# connectors.net
KiCad netlist of a schematic drawn in Altium Designer
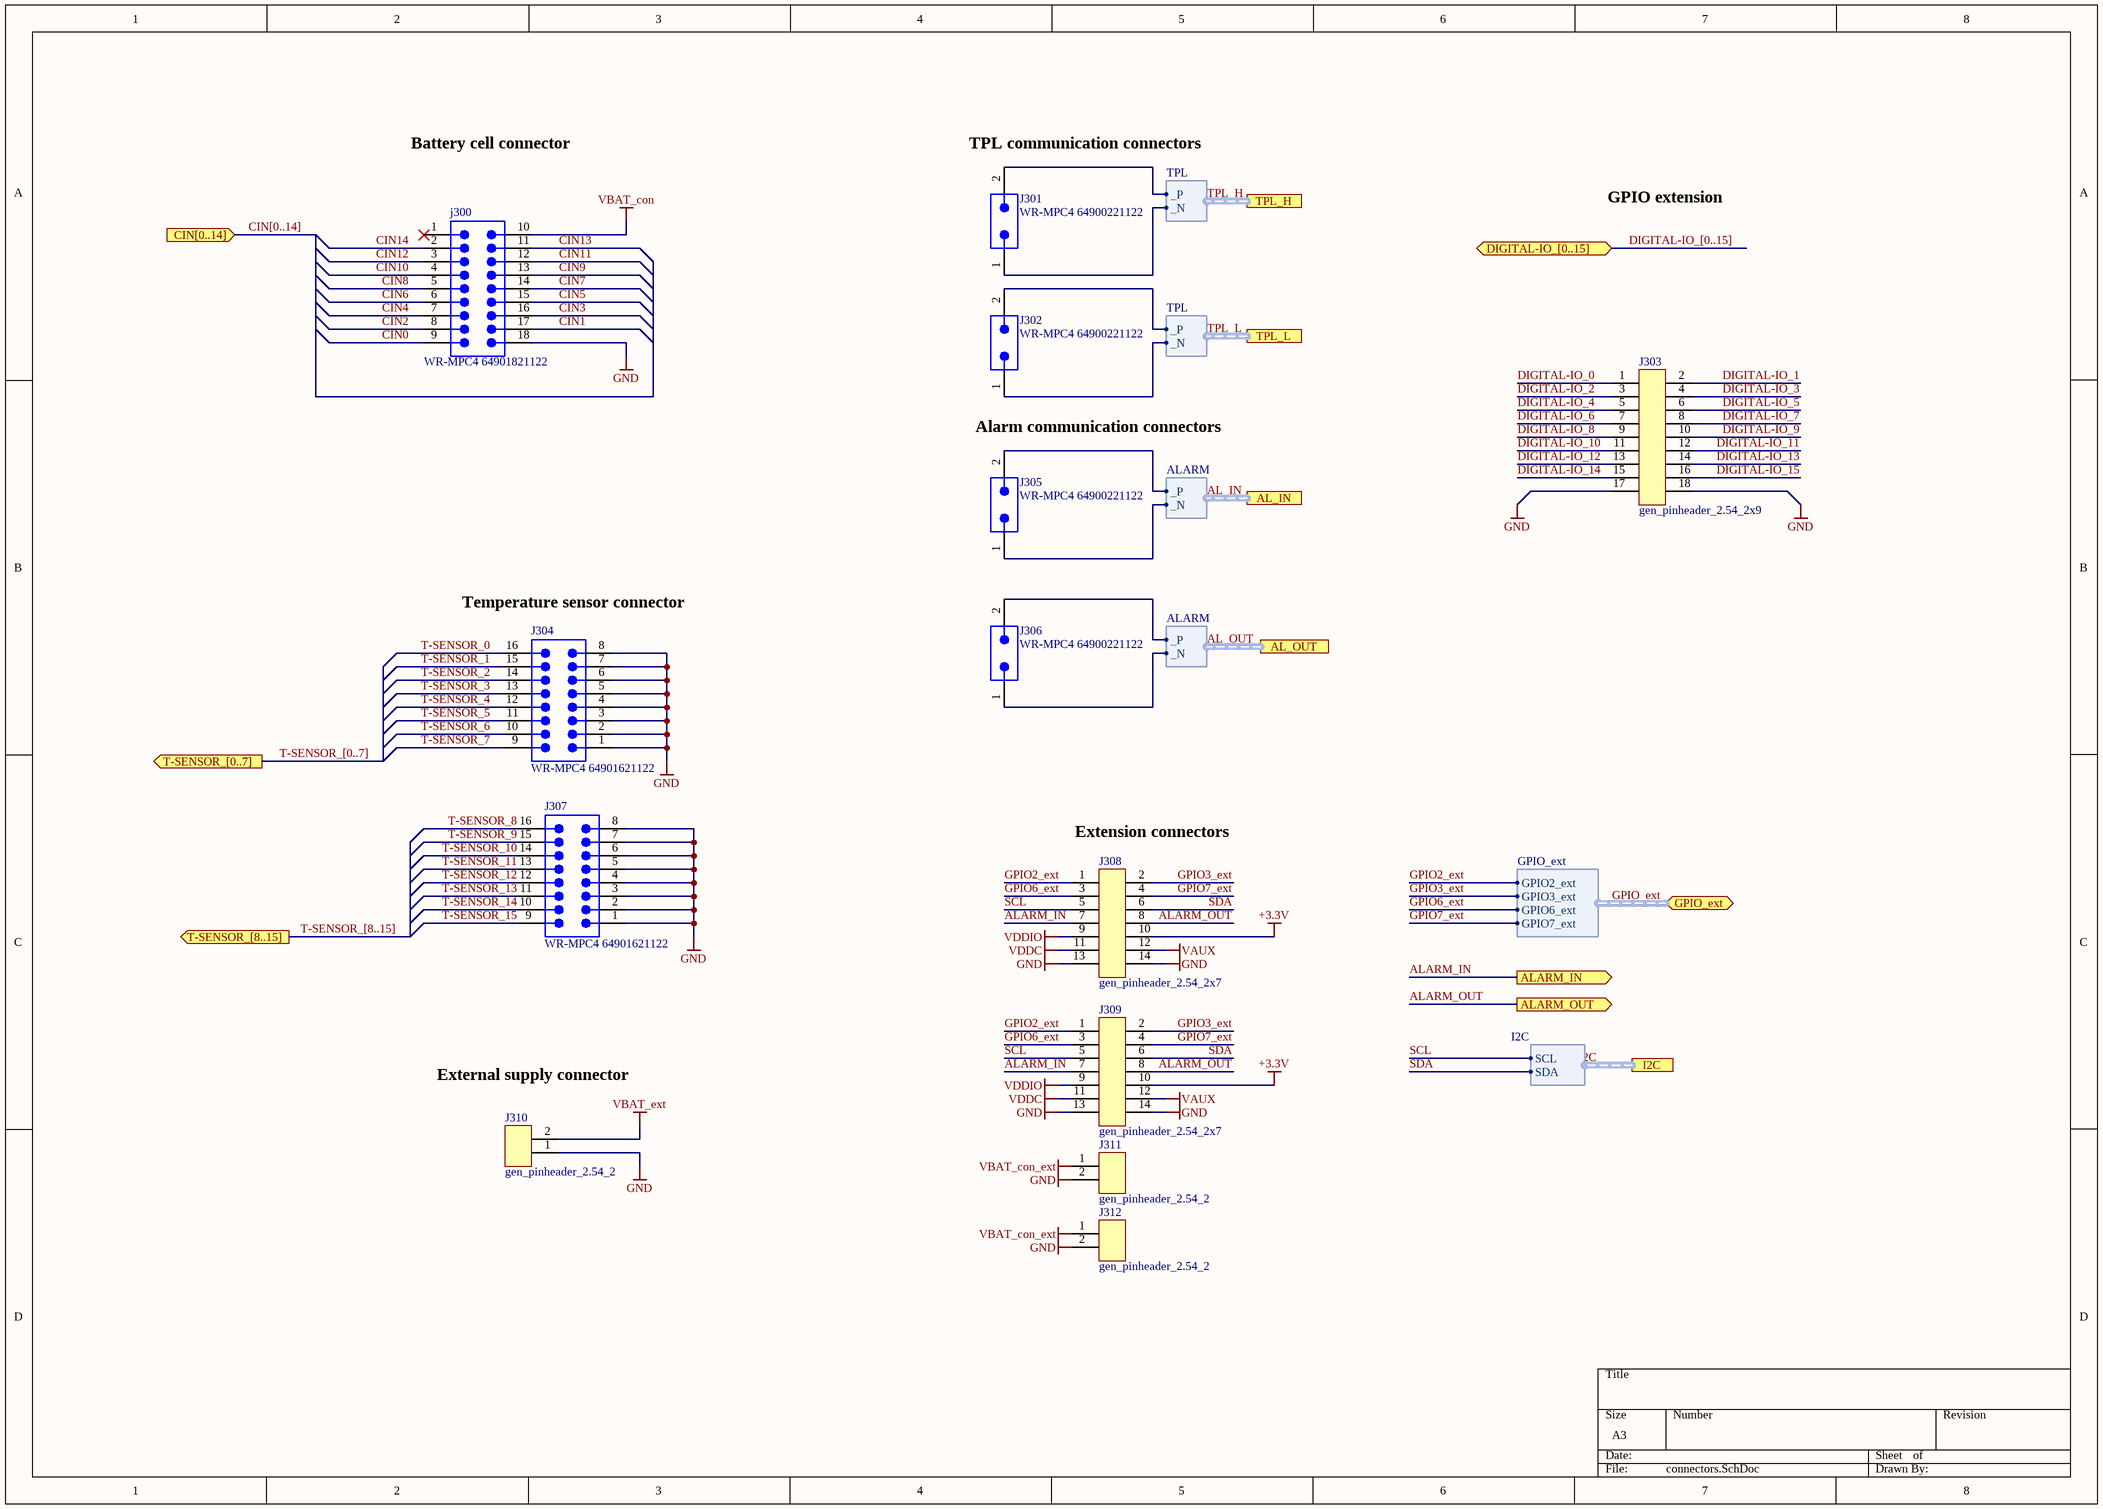
[diagram p0: connectors.SchDoc]

(export (version "E")
  (design (tool "Eeschema 10.0.6"))
  (components
    (comp (ref "j300")
      (value "WR-MPC4 64901821122")
      (footprint "64901821122")
      (libsource (lib "Altium Content Vault") (part "Header_Male_2R_18P(A)"))
    )
    (comp (ref "J301")
      (value "WR-MPC4 64900221122")
      (footprint "64900221122")
      (libsource (lib "Altium Content Vault") (part "Header_Male_2R_02P(A)"))
    )
    (comp (ref "J302")
      (value "WR-MPC4 64900221122")
      (footprint "64900221122")
      (libsource (lib "Altium Content Vault") (part "Header_Male_2R_02P(A)"))
    )
    (comp (ref "J303")
      (value "gen_pinheader_2.54_2x9")
      (footprint "Pinheader_2.54_2x9")
      (description "Standard Pinheader, THD, gerade, 2.54mm, 2-reihig")
      (libsource (lib "OE750") (part "X2x9"))
    )
    (comp (ref "J304")
      (value "WR-MPC4 64901621122")
      (footprint "64901621122")
      (libsource (lib "Altium Content Vault") (part "Header_Male_2R_16P(A)"))
    )
    (comp (ref "J305")
      (value "WR-MPC4 64900221122")
      (footprint "64900221122")
      (libsource (lib "Altium Content Vault") (part "Header_Male_2R_02P(A)"))
    )
    (comp (ref "J306")
      (value "WR-MPC4 64900221122")
      (footprint "64900221122")
      (libsource (lib "Altium Content Vault") (part "Header_Male_2R_02P(A)"))
    )
    (comp (ref "J307")
      (value "WR-MPC4 64901621122")
      (footprint "64901621122")
      (libsource (lib "Altium Content Vault") (part "Header_Male_2R_16P(A)"))
    )
    (comp (ref "J308")
      (value "gen_pinheader_2.54_2x7")
      (footprint "Pinheader_2.54_2x7")
      (description "Standard Pinheader, THD, gerade, 2.54mm, 2-reihig")
      (libsource (lib "OE750") (part "X2x7"))
    )
    (comp (ref "J309")
      (value "gen_pinheader_2.54_2x7")
      (footprint "Pinheader_2.54_2x7")
      (description "Standard Pinheader, THD, gerade, 2.54mm, 2-reihig")
      (libsource (lib "OE750") (part "X2x7"))
    )
    (comp (ref "J310")
      (value "gen_pinheader_2.54_2")
      (footprint "pin_test")
      (description "Standard Pinheader, THD, gerade, 2.54mm")
      (libsource (lib "") (part "X2_1"))
    )
    (comp (ref "J311")
      (value "gen_pinheader_2.54_2")
      (footprint "Pinheader_2.54_2")
      (description "Standard Pinheader, THD, gerade, 2.54mm")
      (libsource (lib "OE750") (part "X2"))
    )
    (comp (ref "J312")
      (value "gen_pinheader_2.54_2")
      (footprint "Pinheader_2.54_2")
      (description "Standard Pinheader, THD, gerade, 2.54mm")
      (libsource (lib "OE750") (part "X2"))
    )
  )
  (nets
    (net (code "7") (name "+3.3V") (class "Default")
      (node (ref "J308") (pin "10") (pintype "passive"))
      (node (ref "J309") (pin "10") (pintype "passive"))
    )
    (net (code "8") (name "/ALARM_IN") (class "Default")
      (node (ref "J308") (pin "7") (pintype "passive"))
      (node (ref "J309") (pin "7") (pintype "passive"))
    )
    (net (code "9") (name "/ALARM_OUT") (class "Default")
      (node (ref "J308") (pin "8") (pintype "passive"))
      (node (ref "J309") (pin "8") (pintype "passive"))
    )
    (net (code "12") (name "/CIN0") (class "Default")
      (node (ref "j300") (pin "9") (pinfunction "9_9") (pintype "passive"))
    )
    (net (code "13") (name "/CIN1") (class "Default")
      (node (ref "j300") (pin "17") (pinfunction "17_17") (pintype "passive"))
    )
    (net (code "14") (name "/CIN2") (class "Default")
      (node (ref "j300") (pin "8") (pinfunction "8_8") (pintype "passive"))
    )
    (net (code "15") (name "/CIN3") (class "Default")
      (node (ref "j300") (pin "16") (pinfunction "16_16") (pintype "passive"))
    )
    (net (code "16") (name "/CIN4") (class "Default")
      (node (ref "j300") (pin "7") (pinfunction "7_7") (pintype "passive"))
    )
    (net (code "17") (name "/CIN5") (class "Default")
      (node (ref "j300") (pin "15") (pinfunction "15_15") (pintype "passive"))
    )
    (net (code "18") (name "/CIN6") (class "Default")
      (node (ref "j300") (pin "6") (pinfunction "6_6") (pintype "passive"))
    )
    (net (code "19") (name "/CIN7") (class "Default")
      (node (ref "j300") (pin "14") (pinfunction "14_14") (pintype "passive"))
    )
    (net (code "20") (name "/CIN8") (class "Default")
      (node (ref "j300") (pin "5") (pinfunction "5_5") (pintype "passive"))
    )
    (net (code "21") (name "/CIN9") (class "Default")
      (node (ref "j300") (pin "13") (pinfunction "13_13") (pintype "passive"))
    )
    (net (code "22") (name "/CIN10") (class "Default")
      (node (ref "j300") (pin "4") (pinfunction "4_4") (pintype "passive"))
    )
    (net (code "23") (name "/CIN11") (class "Default")
      (node (ref "j300") (pin "12") (pinfunction "12_12") (pintype "passive"))
    )
    (net (code "24") (name "/CIN12") (class "Default")
      (node (ref "j300") (pin "3") (pinfunction "3_3") (pintype "passive"))
    )
    (net (code "25") (name "/CIN13") (class "Default")
      (node (ref "j300") (pin "11") (pinfunction "11_11") (pintype "passive"))
    )
    (net (code "26") (name "/CIN14") (class "Default")
      (node (ref "j300") (pin "2") (pinfunction "2_2") (pintype "passive"))
    )
    (net (code "28") (name "/DIGITAL-IO_0") (class "Default")
      (node (ref "J303") (pin "1") (pintype "passive"))
    )
    (net (code "29") (name "/DIGITAL-IO_1") (class "Default")
      (node (ref "J303") (pin "2") (pintype "passive"))
    )
    (net (code "30") (name "/DIGITAL-IO_2") (class "Default")
      (node (ref "J303") (pin "3") (pintype "passive"))
    )
    (net (code "31") (name "/DIGITAL-IO_3") (class "Default")
      (node (ref "J303") (pin "4") (pintype "passive"))
    )
    (net (code "32") (name "/DIGITAL-IO_4") (class "Default")
      (node (ref "J303") (pin "5") (pintype "passive"))
    )
    (net (code "33") (name "/DIGITAL-IO_5") (class "Default")
      (node (ref "J303") (pin "6") (pintype "passive"))
    )
    (net (code "34") (name "/DIGITAL-IO_6") (class "Default")
      (node (ref "J303") (pin "7") (pintype "passive"))
    )
    (net (code "35") (name "/DIGITAL-IO_7") (class "Default")
      (node (ref "J303") (pin "8") (pintype "passive"))
    )
    (net (code "36") (name "/DIGITAL-IO_8") (class "Default")
      (node (ref "J303") (pin "9") (pintype "passive"))
    )
    (net (code "37") (name "/DIGITAL-IO_9") (class "Default")
      (node (ref "J303") (pin "10") (pintype "passive"))
    )
    (net (code "38") (name "/DIGITAL-IO_10") (class "Default")
      (node (ref "J303") (pin "11") (pintype "passive"))
    )
    (net (code "39") (name "/DIGITAL-IO_11") (class "Default")
      (node (ref "J303") (pin "12") (pintype "passive"))
    )
    (net (code "40") (name "/DIGITAL-IO_12") (class "Default")
      (node (ref "J303") (pin "13") (pintype "passive"))
    )
    (net (code "41") (name "/DIGITAL-IO_13") (class "Default")
      (node (ref "J303") (pin "14") (pintype "passive"))
    )
    (net (code "42") (name "/DIGITAL-IO_14") (class "Default")
      (node (ref "J303") (pin "15") (pintype "passive"))
    )
    (net (code "43") (name "/DIGITAL-IO_15") (class "Default")
      (node (ref "J303") (pin "16") (pintype "passive"))
    )
    (net (code "45") (name "/GPIO2_ext") (class "Default")
      (node (ref "J308") (pin "1") (pintype "passive"))
      (node (ref "J309") (pin "1") (pintype "passive"))
    )
    (net (code "46") (name "/GPIO3_ext") (class "Default")
      (node (ref "J308") (pin "2") (pintype "passive"))
      (node (ref "J309") (pin "2") (pintype "passive"))
    )
    (net (code "47") (name "/GPIO6_ext") (class "Default")
      (node (ref "J308") (pin "3") (pintype "passive"))
      (node (ref "J309") (pin "3") (pintype "passive"))
    )
    (net (code "48") (name "/GPIO7_ext") (class "Default")
      (node (ref "J308") (pin "4") (pintype "passive"))
      (node (ref "J309") (pin "4") (pintype "passive"))
    )
    (net (code "51") (name "/SCL") (class "Default")
      (node (ref "J308") (pin "5") (pintype "passive"))
      (node (ref "J309") (pin "5") (pintype "passive"))
    )
    (net (code "52") (name "/SDA") (class "Default")
      (node (ref "J308") (pin "6") (pintype "passive"))
      (node (ref "J309") (pin "6") (pintype "passive"))
    )
    (net (code "53") (name "/T-SENSOR_0") (class "Default")
      (node (ref "J304") (pin "16") (pinfunction "16_16") (pintype "passive"))
    )
    (net (code "54") (name "/T-SENSOR_1") (class "Default")
      (node (ref "J304") (pin "15") (pinfunction "15_15") (pintype "passive"))
    )
    (net (code "55") (name "/T-SENSOR_2") (class "Default")
      (node (ref "J304") (pin "14") (pinfunction "14_14") (pintype "passive"))
    )
    (net (code "56") (name "/T-SENSOR_3") (class "Default")
      (node (ref "J304") (pin "13") (pinfunction "13_13") (pintype "passive"))
    )
    (net (code "57") (name "/T-SENSOR_4") (class "Default")
      (node (ref "J304") (pin "12") (pinfunction "12_12") (pintype "passive"))
    )
    (net (code "58") (name "/T-SENSOR_5") (class "Default")
      (node (ref "J304") (pin "11") (pinfunction "11_11") (pintype "passive"))
    )
    (net (code "59") (name "/T-SENSOR_6") (class "Default")
      (node (ref "J304") (pin "10") (pinfunction "10_10") (pintype "passive"))
    )
    (net (code "60") (name "/T-SENSOR_7") (class "Default")
      (node (ref "J304") (pin "9") (pinfunction "9_9") (pintype "passive"))
    )
    (net (code "61") (name "/T-SENSOR_8") (class "Default")
      (node (ref "J307") (pin "16") (pinfunction "16_16") (pintype "passive"))
    )
    (net (code "62") (name "/T-SENSOR_9") (class "Default")
      (node (ref "J307") (pin "15") (pinfunction "15_15") (pintype "passive"))
    )
    (net (code "63") (name "/T-SENSOR_10") (class "Default")
      (node (ref "J307") (pin "14") (pinfunction "14_14") (pintype "passive"))
    )
    (net (code "64") (name "/T-SENSOR_11") (class "Default")
      (node (ref "J307") (pin "13") (pinfunction "13_13") (pintype "passive"))
    )
    (net (code "65") (name "/T-SENSOR_12") (class "Default")
      (node (ref "J307") (pin "12") (pinfunction "12_12") (pintype "passive"))
    )
    (net (code "66") (name "/T-SENSOR_13") (class "Default")
      (node (ref "J307") (pin "11") (pinfunction "11_11") (pintype "passive"))
    )
    (net (code "67") (name "/T-SENSOR_14") (class "Default")
      (node (ref "J307") (pin "10") (pinfunction "10_10") (pintype "passive"))
    )
    (net (code "68") (name "/T-SENSOR_15") (class "Default")
      (node (ref "J307") (pin "9") (pinfunction "9_9") (pintype "passive"))
    )
    (net (code "73") (name "GND") (class "Default")
      (node (ref "J303") (pin "17") (pintype "passive"))
      (node (ref "J303") (pin "18") (pintype "passive"))
      (node (ref "J304") (pin "1") (pinfunction "1_1") (pintype "passive"))
      (node (ref "J304") (pin "2") (pinfunction "2_2") (pintype "passive"))
      (node (ref "J304") (pin "3") (pinfunction "3_3") (pintype "passive"))
      (node (ref "J304") (pin "4") (pinfunction "4_4") (pintype "passive"))
      (node (ref "J304") (pin "5") (pinfunction "5_5") (pintype "passive"))
      (node (ref "J304") (pin "6") (pinfunction "6_6") (pintype "passive"))
      (node (ref "J304") (pin "7") (pinfunction "7_7") (pintype "passive"))
      (node (ref "J304") (pin "8") (pinfunction "8_8") (pintype "passive"))
      (node (ref "J307") (pin "1") (pinfunction "1_1") (pintype "passive"))
      (node (ref "J307") (pin "2") (pinfunction "2_2") (pintype "passive"))
      (node (ref "J307") (pin "3") (pinfunction "3_3") (pintype "passive"))
      (node (ref "J307") (pin "4") (pinfunction "4_4") (pintype "passive"))
      (node (ref "J307") (pin "5") (pinfunction "5_5") (pintype "passive"))
      (node (ref "J307") (pin "6") (pinfunction "6_6") (pintype "passive"))
      (node (ref "J307") (pin "7") (pinfunction "7_7") (pintype "passive"))
      (node (ref "J307") (pin "8") (pinfunction "8_8") (pintype "passive"))
      (node (ref "J308") (pin "13") (pintype "passive"))
      (node (ref "J308") (pin "14") (pintype "passive"))
      (node (ref "J309") (pin "13") (pintype "passive"))
      (node (ref "J309") (pin "14") (pintype "passive"))
      (node (ref "J310") (pin "1") (pintype "passive"))
      (node (ref "J311") (pin "2") (pintype "passive"))
      (node (ref "J312") (pin "2") (pintype "passive"))
      (node (ref "j300") (pin "18") (pinfunction "18_18") (pintype "passive"))
    )
    (net (code "74") (name "VAUX") (class "Default")
      (node (ref "J308") (pin "12") (pintype "passive"))
      (node (ref "J309") (pin "12") (pintype "passive"))
    )
    (net (code "75") (name "VBAT_con") (class "Default")
      (node (ref "j300") (pin "10") (pinfunction "10_10") (pintype "passive"))
    )
    (net (code "76") (name "VBAT_con_ext") (class "Default")
      (node (ref "J311") (pin "1") (pintype "passive"))
      (node (ref "J312") (pin "1") (pintype "passive"))
    )
    (net (code "77") (name "VBAT_ext") (class "Default") (node (ref "J310") (pin "2") (pintype "passive")))
    (net (code "78") (name "VDDC") (class "Default")
      (node (ref "J308") (pin "11") (pintype "passive"))
      (node (ref "J309") (pin "11") (pintype "passive"))
    )
    (net (code "79") (name "VDDIO") (class "Default")
      (node (ref "J308") (pin "9") (pintype "passive"))
      (node (ref "J309") (pin "9") (pintype "passive"))
    )
    (net (code "80") (name "unconnected-(J301-Pad1)") (class "Default")
      (node (ref "J301") (pin "1") (pinfunction "1_1") (pintype "passive"))
    )
    (net (code "81") (name "unconnected-(J301-Pad2)") (class "Default")
      (node (ref "J301") (pin "2") (pinfunction "2_2") (pintype "passive"))
    )
    (net (code "82") (name "unconnected-(J302-Pad1)") (class "Default")
      (node (ref "J302") (pin "1") (pinfunction "1_1") (pintype "passive"))
    )
    (net (code "83") (name "unconnected-(J302-Pad2)") (class "Default")
      (node (ref "J302") (pin "2") (pinfunction "2_2") (pintype "passive"))
    )
    (net (code "84") (name "unconnected-(J305-Pad1)") (class "Default")
      (node (ref "J305") (pin "1") (pinfunction "1_1") (pintype "passive"))
    )
    (net (code "85") (name "unconnected-(J305-Pad2)") (class "Default")
      (node (ref "J305") (pin "2") (pinfunction "2_2") (pintype "passive"))
    )
    (net (code "86") (name "unconnected-(J306-Pad1)") (class "Default")
      (node (ref "J306") (pin "1") (pinfunction "1_1") (pintype "passive"))
    )
    (net (code "87") (name "unconnected-(J306-Pad2)") (class "Default")
      (node (ref "J306") (pin "2") (pinfunction "2_2") (pintype "passive"))
    )
    (net (code "88") (name "unconnected-(j300-Pad1)") (class "Default")
      (node (ref "j300") (pin "1") (pinfunction "1_1") (pintype "passive+no_connect"))
    )
  )
)
